# Amplifier_Sheet.net
KiCad netlist of a schematic drawn in Altium Designer
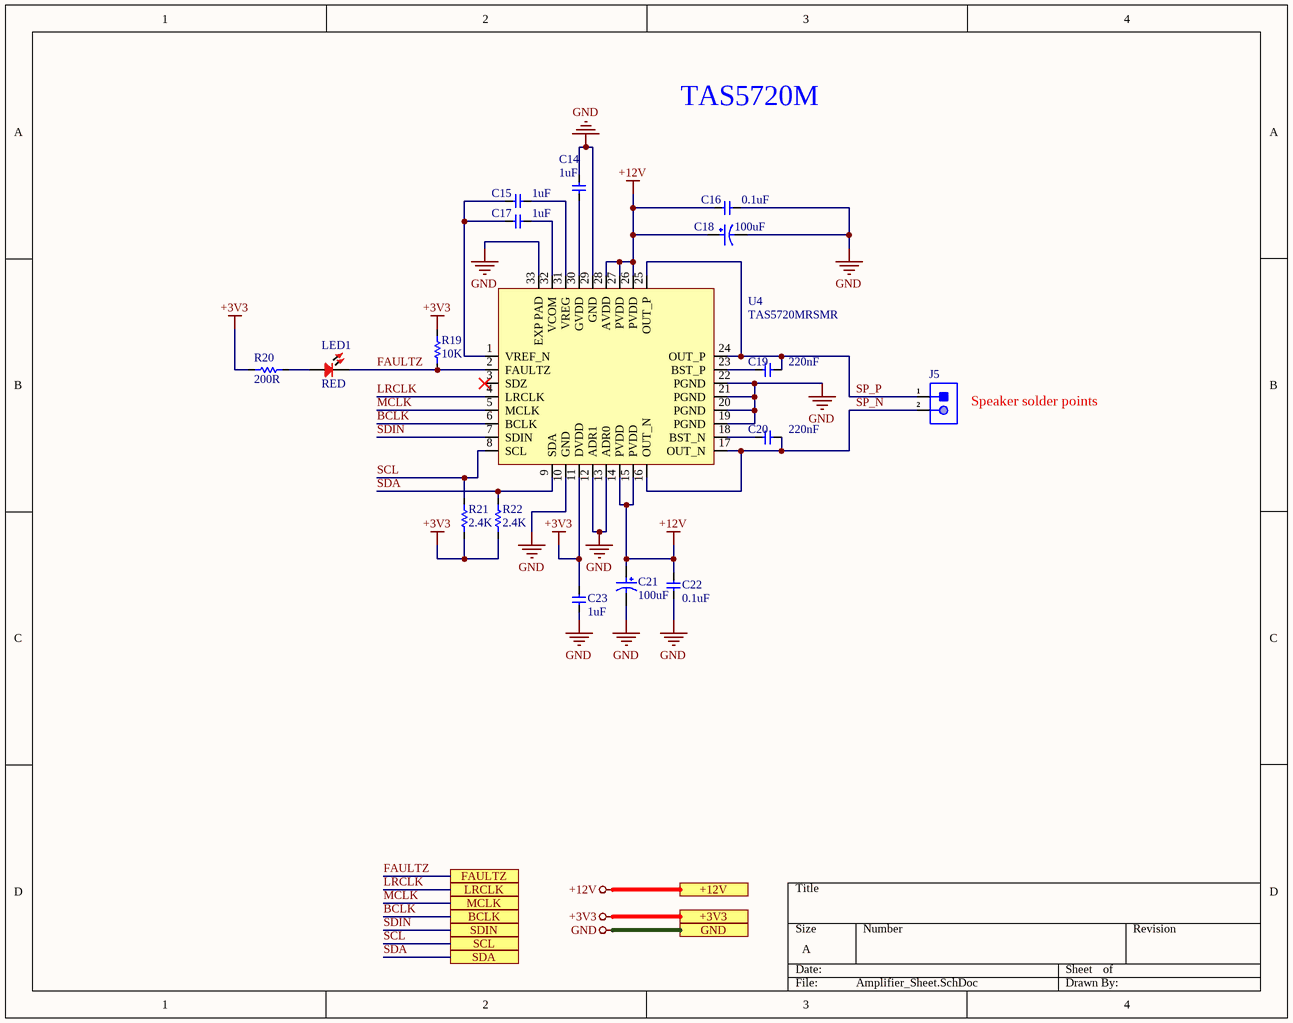
[diagram p0: Amplifier_Sheet.SchDoc]

(export (version "E")
  (design (tool "Eeschema 10.0.6"))
  (components
    (comp (ref "C14")
      (value "1uF")
      (footprint "Cap-0603")
      (description "CAP CER 1UF 25V X5R 0603")
      (fields
        (field (name "MANUFACTURER") "Yageo")
        (field (name "MANUFACTURER PART NUMBER") "CC0603KRX5R8BB105")
      )
      (libsource (lib "DigitalAzanClock") (part "CC0603KRX5R8BB105"))
    )
    (comp (ref "C15")
      (value "1uF")
      (footprint "Cap-0603")
      (description "CAP CER 1UF 25V X5R 0603")
      (fields
        (field (name "MANUFACTURER") "Yageo")
        (field (name "MANUFACTURER PART NUMBER") "CC0603KRX5R8BB105")
      )
      (libsource (lib "DigitalAzanClock") (part "CC0603KRX5R8BB105"))
    )
    (comp (ref "C16")
      (value "0.1uF")
      (footprint "Cap-0603")
      (description "CAP CER 0.1UF 100V X7R 0603")
      (fields
        (field (name "MANUFACTURER") "Yageo")
        (field (name "MANUFACTURER PART NUMBER") "CC0603KRX7R0BB104")
      )
      (libsource (lib "DigitalAzanClock") (part "CC0603KRX7R0BB104"))
    )
    (comp (ref "C17")
      (value "1uF")
      (footprint "Cap-0603")
      (description "CAP CER 1UF 25V X5R 0603")
      (fields
        (field (name "MANUFACTURER") "Yageo")
        (field (name "MANUFACTURER PART NUMBER") "CC0603KRX5R8BB105")
      )
      (libsource (lib "DigitalAzanClock") (part "CC0603KRX5R8BB105"))
    )
    (comp (ref "C18")
      (value "100uF")
      (footprint "RVT1H101M0607")
      (description "100uF 50V ±20% SMD,D6.3xL7.7mm Aluminum Electrolytic Capacitors - SMD ROHS")
      (fields
        (field (name "MANUFACTURER") "ROQANG")
        (field (name "MANUFACTURER PART NUMBER") "RVT1H101M0607")
      )
      (libsource (lib "") (part "RVT1H101M0607_1"))
    )
    (comp (ref "C19")
      (value "220nF")
      (footprint "Cap-0402")
      (description "CAP CER 0.22UF 25V X5R 0402")
      (fields
        (field (name "MANUFACTURER") "Yageo")
        (field (name "MANUFACTURER PART NUMBER") "CC0402KRX5R8BB224")
      )
      (libsource (lib "DigitalAzanClock") (part "CC0402KRX5R8BB224"))
    )
    (comp (ref "C20")
      (value "220nF")
      (footprint "Cap-0402")
      (description "CAP CER 0.22UF 25V X5R 0402")
      (fields
        (field (name "MANUFACTURER") "Yageo")
        (field (name "MANUFACTURER PART NUMBER") "CC0402KRX5R8BB224")
      )
      (libsource (lib "DigitalAzanClock") (part "CC0402KRX5R8BB224"))
    )
    (comp (ref "C21")
      (value "100uF")
      (footprint "RVT1H101M0607")
      (description "100uF 50V ±20% SMD,D6.3xL7.7mm Aluminum Electrolytic Capacitors - SMD ROHS")
      (fields
        (field (name "MANUFACTURER") "ROQANG")
        (field (name "MANUFACTURER PART NUMBER") "RVT1H101M0607")
      )
      (libsource (lib "DigitalAzanClock") (part "RVT1H101M0607"))
    )
    (comp (ref "C22")
      (value "0.1uF")
      (footprint "Cap-0603")
      (description "CAP CER 0.1UF 100V X7R 0603")
      (fields
        (field (name "MANUFACTURER") "Yageo")
        (field (name "MANUFACTURER PART NUMBER") "CC0603KRX7R0BB104")
      )
      (libsource (lib "DigitalAzanClock") (part "CC0603KRX7R0BB104"))
    )
    (comp (ref "C23")
      (value "1uF")
      (footprint "Cap-0603")
      (description "CAP CER 1UF 25V X5R 0603")
      (fields
        (field (name "MANUFACTURER") "Yageo")
        (field (name "MANUFACTURER PART NUMBER") "CC0603KRX5R8BB105")
      )
      (libsource (lib "DigitalAzanClock") (part "CC0603KRX5R8BB105"))
    )
    (comp (ref "J5")
      (value "2P THrough Hole Pads")
      (footprint "2P THrough Hole Pads")
      (description "Wire Connecting Pad")
      (libsource (lib "DigitalAzanClock") (part "2P THrough Hole Pads"))
    )
    (comp (ref "LED1")
      (value "RED")
      (footprint "LED-0603")
      (description "RED LED 0603 Light Emitting Diodes")
      (fields
        (field (name "MANUFACTURER") "Foshan NationStar Optoelectronics")
        (field (name "MANUFACTURER PART NUMBER") "NCD0603R3")
      )
      (libsource (lib "DigitalAzanClock") (part "NCD0603R3"))
    )
    (comp (ref "R19")
      (value "10K")
      (footprint "Res-0603")
      (description "RES SMD 10K OHM 0.1% 1/10W 0603")
      (fields
        (field (name "MANUFACTURER") "Yageo")
        (field (name "MANUFACTURER PART NUMBER") "RT0603BRD0710KL")
      )
      (libsource (lib "DigitalAzanClock") (part "RT0603BRD0710KL"))
    )
    (comp (ref "R20")
      (value "200R")
      (footprint "Res-0402")
      (description "62.5mW Thick Film Resistors 50V ±100ppm/℃ ±1% 200Ω 0402 Chip Resistor - Surface Mount ROHS")
      (fields
        (field (name "MANUFACTURER") "FOJAN")
        (field (name "MANUFACTURER PART NUMBER") "FRC0402F2000TS")
      )
      (libsource (lib "DigitalAzanClock") (part "FRC0402F2000TS"))
    )
    (comp (ref "R21")
      (value "2.4K")
      (footprint "Res-0402")
      (description "62.5mW Thick Film Resistors 50V ±100ppm/℃ ±1% 2.4kΩ 0402 Chip Resistor - Surface Mount ROHS")
      (fields
        (field (name "MANUFACTURER") "UNI ROYAL")
        (field (name "MANUFACTURER PART NUMBER") "0402WGF2401TCE")
      )
      (libsource (lib "DigitalAzanClock") (part "0402WGF2401TCE"))
    )
    (comp (ref "R22")
      (value "2.4K")
      (footprint "Res-0402")
      (description "62.5mW Thick Film Resistors 50V ±100ppm/℃ ±1% 2.4kΩ 0402 Chip Resistor - Surface Mount ROHS")
      (fields
        (field (name "MANUFACTURER") "UNI ROYAL")
        (field (name "MANUFACTURER PART NUMBER") "0402WGF2401TCE")
      )
      (libsource (lib "DigitalAzanClock") (part "0402WGF2401TCE"))
    )
    (comp (ref "U4")
      (value "TAS5720MRSMR")
      (footprint "TAS5720M")
      (description "20Wx1@4Ω VQFN-32(4x4) Audio Power OpAmps ROHS")
      (fields (field (name "MANUFACTURER") "Texas Instruments") (field (name "LCSC PART NUMBER") "C5214961"))
      (libsource (lib "DigitalAzanClock") (part "TAS5720MRSMR"))
    )
  )
  (nets
    (net (code "1") (name "+3V3") (class "Default")
      (node (ref "C23") (pin "2") (pinfunction "2_2") (pintype "passive"))
      (node (ref "R19") (pin "1") (pinfunction "1_1") (pintype "passive"))
      (node (ref "R20") (pin "1") (pinfunction "1_1") (pintype "passive"))
      (node (ref "R21") (pin "1") (pinfunction "1_1") (pintype "passive"))
      (node (ref "R22") (pin "1") (pinfunction "1_1") (pintype "passive"))
      (node (ref "U4") (pin "11") (pinfunction "DVDD_11") (pintype "passive"))
    )
    (net (code "2") (name "+12V") (class "Default")
      (node (ref "C16") (pin "1") (pinfunction "1_1") (pintype "passive"))
      (node (ref "C18") (pin "1") (pintype "passive"))
      (node (ref "C21") (pin "1") (pintype "passive"))
      (node (ref "C22") (pin "1") (pinfunction "1_1") (pintype "passive"))
      (node (ref "U4") (pin "14") (pinfunction "PVDD_14") (pintype "passive"))
      (node (ref "U4") (pin "15") (pinfunction "PVDD_15") (pintype "passive"))
      (node (ref "U4") (pin "26") (pinfunction "PVDD_26") (pintype "passive"))
      (node (ref "U4") (pin "27") (pinfunction "PVDD_27") (pintype "passive"))
      (node (ref "U4") (pin "28") (pinfunction "AVDD_28") (pintype "passive"))
    )
    (net (code "3") (name "/BCLK") (class "Default")
      (node (ref "U4") (pin "6") (pinfunction "BCLK_6") (pintype "passive"))
    )
    (net (code "4") (name "/FAULTZ") (class "Default")
      (node (ref "LED1") (pin "2") (pinfunction "2_2") (pintype "passive"))
      (node (ref "R19") (pin "2") (pinfunction "2_2") (pintype "passive"))
      (node (ref "U4") (pin "2") (pinfunction "FAULTZ_2") (pintype "passive"))
    )
    (net (code "5") (name "/LRCLK") (class "Default")
      (node (ref "U4") (pin "4") (pinfunction "LRCLK_4") (pintype "passive"))
    )
    (net (code "6") (name "/MCLK") (class "Default")
      (node (ref "U4") (pin "5") (pinfunction "MCLK_5") (pintype "passive"))
    )
    (net (code "7") (name "/SCL") (class "Default")
      (node (ref "R21") (pin "2") (pinfunction "2_2") (pintype "passive"))
      (node (ref "U4") (pin "8") (pinfunction "SCL_8") (pintype "passive"))
    )
    (net (code "8") (name "/SDA") (class "Default")
      (node (ref "R22") (pin "2") (pinfunction "2_2") (pintype "passive"))
      (node (ref "U4") (pin "9") (pinfunction "SDA_9") (pintype "passive"))
    )
    (net (code "9") (name "/SDIN") (class "Default")
      (node (ref "U4") (pin "7") (pinfunction "SDIN_7") (pintype "passive"))
    )
    (net (code "10") (name "/SP_N") (class "Default")
      (node (ref "C20") (pin "2") (pinfunction "2_2") (pintype "passive"))
      (node (ref "J5") (pin "2") (pinfunction "2_2") (pintype "passive"))
      (node (ref "U4") (pin "16") (pinfunction "OUT_N_16") (pintype "passive"))
      (node (ref "U4") (pin "17") (pinfunction "OUT_N_17") (pintype "passive"))
    )
    (net (code "11") (name "/SP_P") (class "Default")
      (node (ref "C19") (pin "2") (pinfunction "2_2") (pintype "passive"))
      (node (ref "J5") (pin "1") (pinfunction "1_1") (pintype "passive"))
      (node (ref "U4") (pin "24") (pinfunction "OUT_P_24") (pintype "passive"))
      (node (ref "U4") (pin "25") (pinfunction "OUT_P_25") (pintype "passive"))
    )
    (net (code "12") (name "GND") (class "Default")
      (node (ref "C14") (pin "2") (pinfunction "2_2") (pintype "passive"))
      (node (ref "C16") (pin "2") (pinfunction "2_2") (pintype "passive"))
      (node (ref "C18") (pin "2") (pintype "passive"))
      (node (ref "C21") (pin "2") (pintype "passive"))
      (node (ref "C22") (pin "2") (pinfunction "2_2") (pintype "passive"))
      (node (ref "C23") (pin "1") (pinfunction "1_1") (pintype "passive"))
      (node (ref "U4") (pin "10") (pinfunction "GND_10") (pintype "passive"))
      (node (ref "U4") (pin "12") (pinfunction "ADR1_12") (pintype "passive"))
      (node (ref "U4") (pin "13") (pinfunction "ADR0_13") (pintype "passive"))
      (node (ref "U4") (pin "19") (pinfunction "PGND_19") (pintype "passive"))
      (node (ref "U4") (pin "20") (pinfunction "PGND_20") (pintype "passive"))
      (node (ref "U4") (pin "21") (pinfunction "PGND_21") (pintype "passive"))
      (node (ref "U4") (pin "22") (pinfunction "PGND_22") (pintype "passive"))
      (node (ref "U4") (pin "29") (pinfunction "GND_29") (pintype "passive"))
      (node (ref "U4") (pin "33") (pinfunction "EXP_PAD_33") (pintype "passive"))
    )
    (net (code "13") (name "Net-(LED1-Pad1)") (class "Default")
      (node (ref "LED1") (pin "1") (pinfunction "1_1") (pintype "passive"))
      (node (ref "R20") (pin "2") (pinfunction "2_2") (pintype "passive"))
    )
    (net (code "14") (name "Net-(U4-BST_N)") (class "Default")
      (node (ref "C20") (pin "1") (pinfunction "1_1") (pintype "passive"))
      (node (ref "U4") (pin "18") (pinfunction "BST_N_18") (pintype "passive"))
    )
    (net (code "15") (name "Net-(U4-BST_P)") (class "Default")
      (node (ref "C19") (pin "1") (pinfunction "1_1") (pintype "passive"))
      (node (ref "U4") (pin "23") (pinfunction "BST_P_23") (pintype "passive"))
    )
    (net (code "16") (name "Net-(U4-GVDD)") (class "Default")
      (node (ref "C14") (pin "1") (pinfunction "1_1") (pintype "passive"))
      (node (ref "U4") (pin "30") (pinfunction "GVDD_30") (pintype "passive"))
    )
    (net (code "17") (name "Net-(U4-VCOM)") (class "Default")
      (node (ref "C17") (pin "2") (pinfunction "2_2") (pintype "passive"))
      (node (ref "U4") (pin "32") (pinfunction "VCOM_32") (pintype "passive"))
    )
    (net (code "18") (name "Net-(U4-VREF_N)") (class "Default")
      (node (ref "C15") (pin "1") (pinfunction "1_1") (pintype "passive"))
      (node (ref "C17") (pin "1") (pinfunction "1_1") (pintype "passive"))
      (node (ref "U4") (pin "1") (pinfunction "VREF_N_1") (pintype "passive"))
    )
    (net (code "19") (name "Net-(U4-VREG)") (class "Default")
      (node (ref "C15") (pin "2") (pinfunction "2_2") (pintype "passive"))
      (node (ref "U4") (pin "31") (pinfunction "VREG_31") (pintype "passive"))
    )
    (net (code "20") (name "unconnected-(U4-SDZ-Pad3)") (class "Default")
      (node (ref "U4") (pin "3") (pinfunction "SDZ_3") (pintype "passive+no_connect"))
    )
  )
)
